# 4_78.net
KiCad netlist of a schematic drawn in EasyEDA
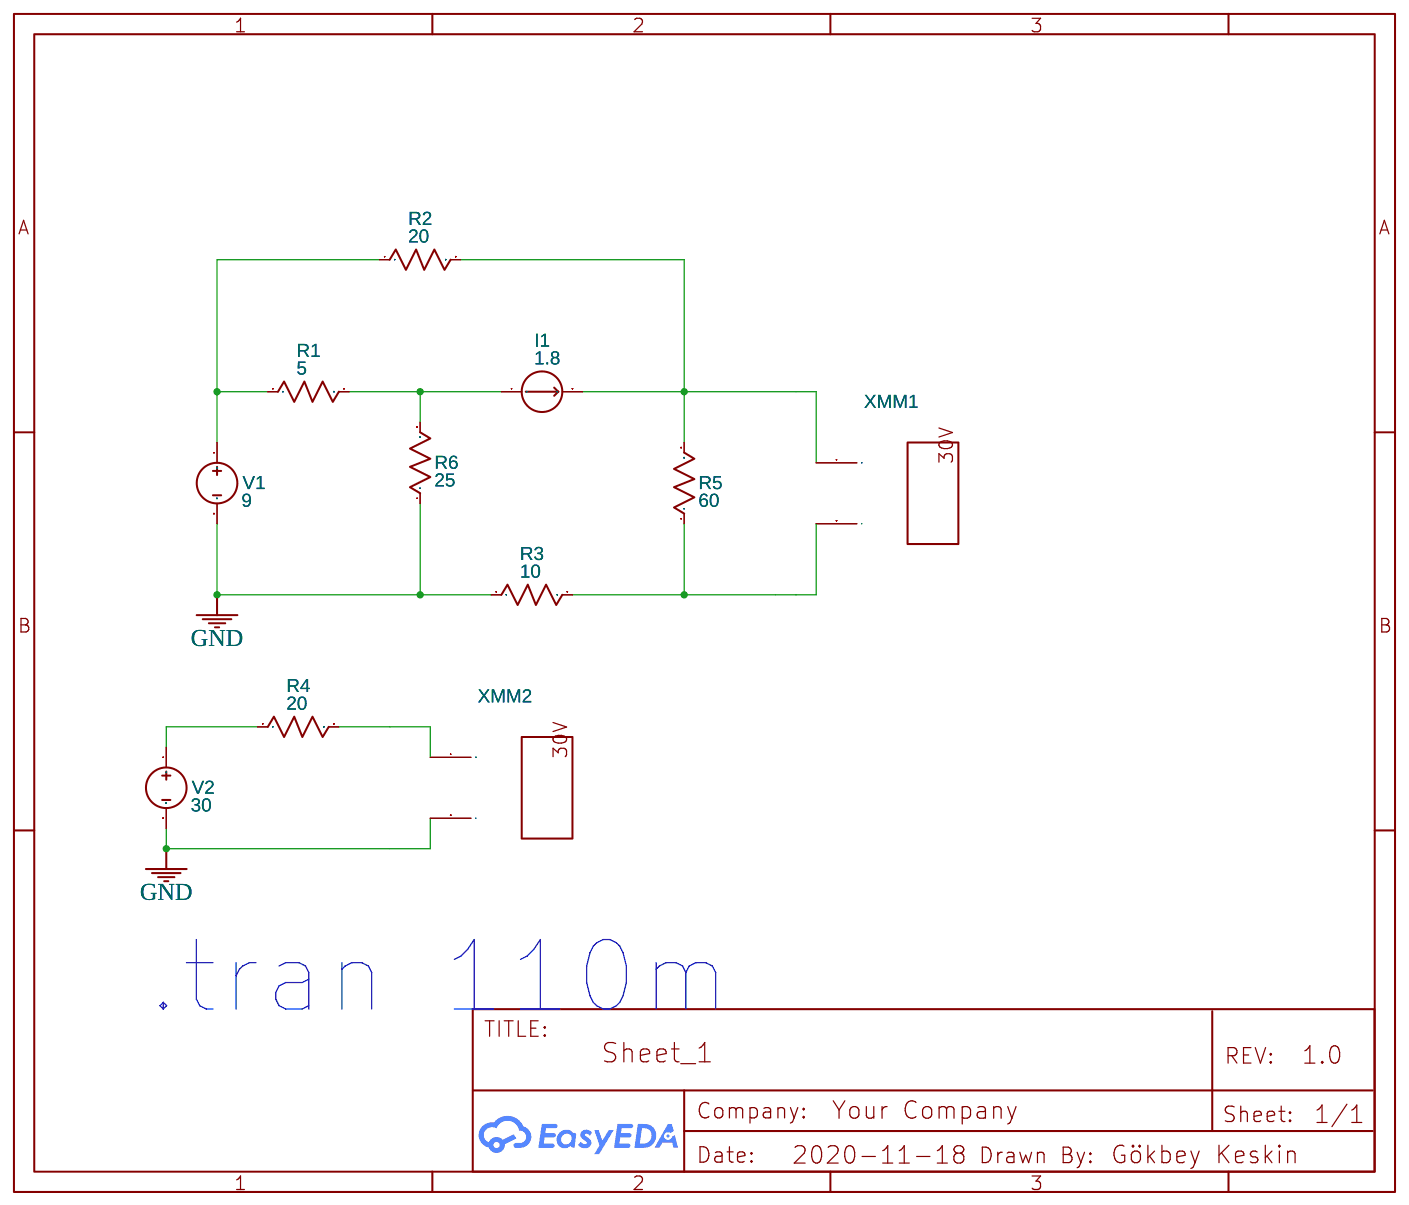
[diagram p0: schematic sheet]

(export (version "E")
  (design (tool "Eeschema 10.0.6"))
  (components
    (comp (ref "I1") (value "1.8") (libsource (lib "") (part "IDC")))
    (comp (ref "R1") (value "5") (libsource (lib "") (part "Resistor_US")))
    (comp (ref "R2") (value "20") (libsource (lib "") (part "Resistor_US")))
    (comp (ref "R3") (value "10") (libsource (lib "") (part "Resistor_US")))
    (comp (ref "R4") (value "20") (libsource (lib "") (part "Resistor_US")))
    (comp (ref "R5") (value "60") (libsource (lib "") (part "Resistor_US_1")))
    (comp (ref "R6") (value "25") (libsource (lib "") (part "Resistor_US_1")))
    (comp (ref "V1") (value "9") (libsource (lib "") (part "VDC")))
    (comp (ref "V2") (value "30") (libsource (lib "") (part "VDC")))
    (comp (ref "XMM1") (value "Multimeter") (libsource (lib "") (part "MULTIMETER")))
    (comp (ref "XMM2") (value "Multimeter") (libsource (lib "") (part "MULTIMETER")))
  )
  (nets
    (net (code "1") (name "GND") (class "Default")
      (node (ref "R3") (pin "1") (pinfunction "1_1") (pintype "unspecified"))
      (node (ref "R6") (pin "1") (pinfunction "1_1") (pintype "unspecified"))
      (node (ref "V1") (pin "2") (pinfunction "2_2") (pintype "unspecified"))
      (node (ref "V2") (pin "2") (pinfunction "2_2") (pintype "unspecified"))
      (node (ref "XMM2") (pin "2") (pinfunction "I_2") (pintype "unspecified"))
    )
    (net (code "2") (name "Net-(I1-Pad1)") (class "Default")
      (node (ref "I1") (pin "1") (pinfunction "1_1") (pintype "unspecified"))
      (node (ref "R1") (pin "2") (pinfunction "2_2") (pintype "unspecified"))
      (node (ref "R6") (pin "2") (pinfunction "2_2") (pintype "unspecified"))
    )
    (net (code "3") (name "Net-(R1-Pad1)") (class "Default")
      (node (ref "R1") (pin "1") (pinfunction "1_1") (pintype "unspecified"))
      (node (ref "R2") (pin "1") (pinfunction "1_1") (pintype "unspecified"))
      (node (ref "V1") (pin "1") (pinfunction "1_1") (pintype "unspecified"))
    )
    (net (code "4") (name "Net-(R4-Pad1)") (class "Default")
      (node (ref "R4") (pin "1") (pinfunction "1_1") (pintype "unspecified"))
      (node (ref "V2") (pin "1") (pinfunction "1_1") (pintype "unspecified"))
    )
    (net (code "5") (name "Net-(XMM1-+)") (class "Default")
      (node (ref "I1") (pin "2") (pinfunction "2_2") (pintype "unspecified"))
      (node (ref "R2") (pin "2") (pinfunction "2_2") (pintype "unspecified"))
      (node (ref "R5") (pin "2") (pinfunction "2_2") (pintype "unspecified"))
      (node (ref "XMM1") (pin "1") (pinfunction "+_1") (pintype "unspecified"))
    )
    (net (code "6") (name "Net-(XMM1-I)") (class "Default")
      (node (ref "R3") (pin "2") (pinfunction "2_2") (pintype "unspecified"))
      (node (ref "R5") (pin "1") (pinfunction "1_1") (pintype "unspecified"))
      (node (ref "XMM1") (pin "2") (pinfunction "I_2") (pintype "unspecified"))
    )
    (net (code "7") (name "Net-(XMM2-+)") (class "Default")
      (node (ref "R4") (pin "2") (pinfunction "2_2") (pintype "unspecified"))
      (node (ref "XMM2") (pin "1") (pinfunction "+_1") (pintype "unspecified"))
    )
  )
)
